# marqee_attiny85_new.net
KiCad netlist of a schematic drawn in EAGLE
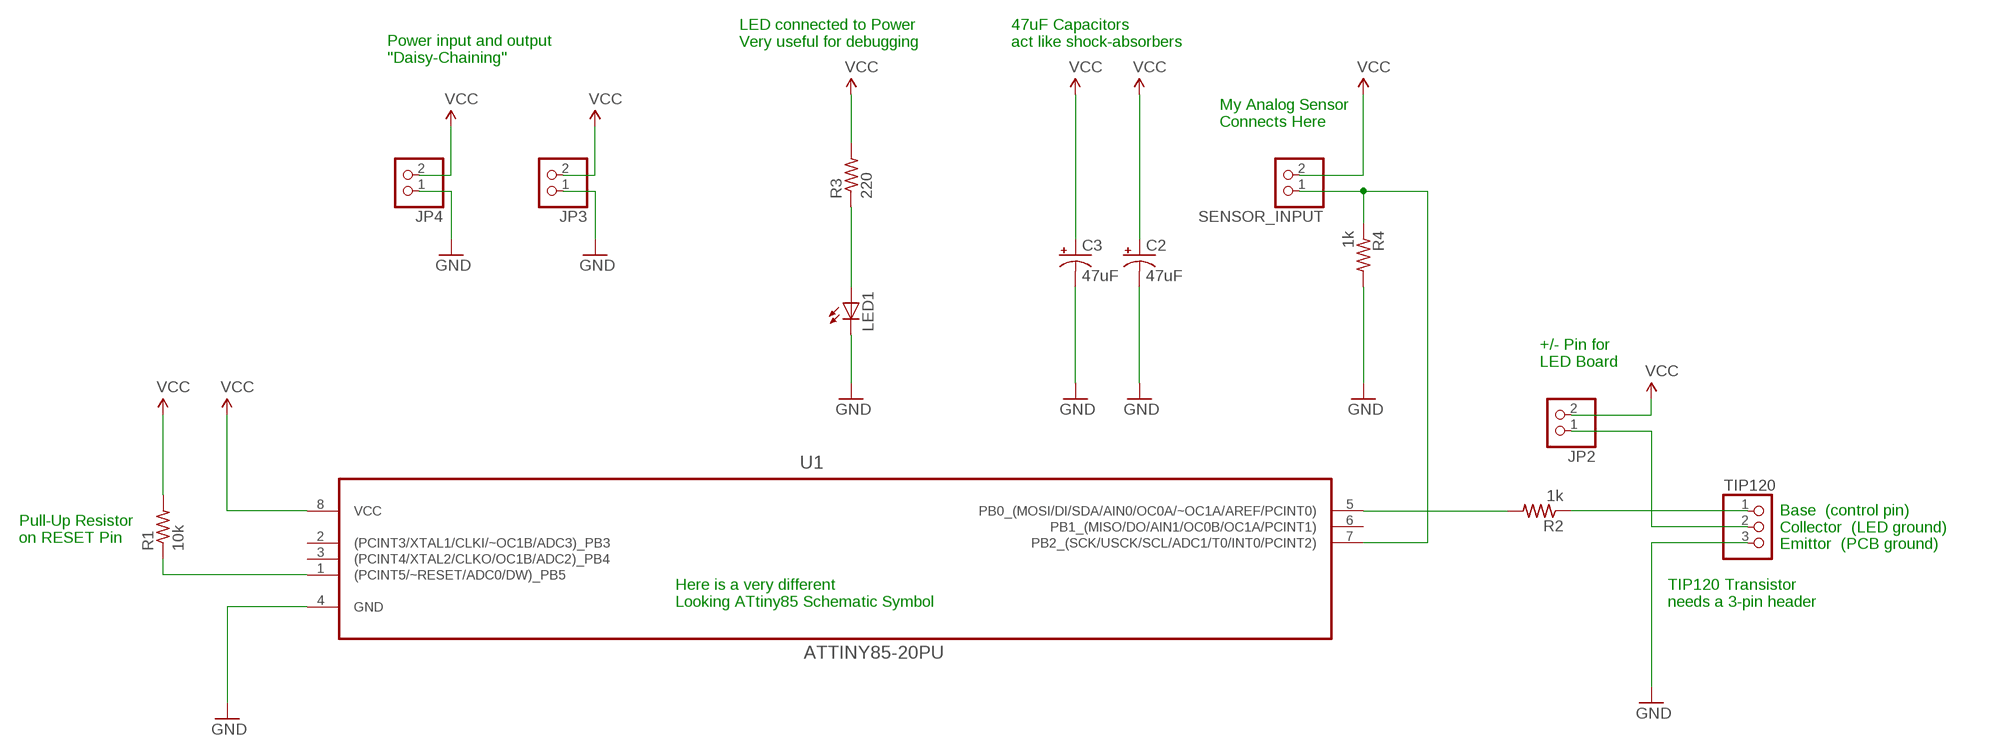
[diagram p0: schematic, sheet 1]

(export (version "E")
  (design (tool "Eeschema 10.0.6"))
  (components
    (comp (ref "C2")
      (value "47uF")
      (footprint "eagle-import:E5-8,5")
      (libsource (lib "eagle-import") (part "CPOL-USE5-8.5"))
    )
    (comp (ref "C3")
      (value "47uF")
      (footprint "eagle-import:E5-8,5")
      (libsource (lib "eagle-import") (part "CPOL-USE5-8.5"))
    )
    (comp (ref "JP2")
      (value "PINHD-1X2")
      (footprint "eagle-import:1X02")
      (libsource (lib "eagle-import") (part "PINHD-1X2"))
    )
    (comp (ref "JP3")
      (value "PINHD-1X2")
      (footprint "eagle-import:1X02")
      (libsource (lib "eagle-import") (part "PINHD-1X2"))
    )
    (comp (ref "JP4")
      (value "PINHD-1X2")
      (footprint "eagle-import:1X02")
      (libsource (lib "eagle-import") (part "PINHD-1X2"))
    )
    (comp (ref "LED1")
      (value "LED5MM")
      (footprint "eagle-import:LED5MM")
      (libsource (lib "eagle-import") (part "LED5MM"))
    )
    (comp (ref "R1")
      (value "10k")
      (footprint "eagle-import:0207_10")
      (libsource (lib "eagle-import") (part "R-US_0207/10"))
    )
    (comp (ref "R2")
      (value "1k")
      (footprint "eagle-import:0207_10")
      (libsource (lib "eagle-import") (part "R-US_0207/10"))
    )
    (comp (ref "R3")
      (value "220")
      (footprint "eagle-import:0207_10")
      (libsource (lib "eagle-import") (part "R-US_0207/10"))
    )
    (comp (ref "R4")
      (value "1k")
      (footprint "eagle-import:0207_10")
      (libsource (lib "eagle-import") (part "R-US_0207/10"))
    )
    (comp (ref "SENSOR_INPUT")
      (value "PINHD-1X2")
      (footprint "eagle-import:1X02")
      (libsource (lib "eagle-import") (part "PINHD-1X2"))
    )
    (comp (ref "TIP120")
      (value "PINHD-1X3")
      (footprint "eagle-import:1X03")
      (libsource (lib "eagle-import") (part "PINHD-1X3"))
    )
    (comp (ref "U1")
      (value "ATTINY85-20PU")
      (footprint "eagle-import:DIP254P762X533-8")
      (libsource (lib "eagle-import") (part "ATTINY85-20PU"))
    )
  )
  (nets
    (net (code "1") (name "GND") (class "Default")
      (node (ref "C2") (pin "-") (pinfunction "-_-") (pintype "passive"))
      (node (ref "C3") (pin "-") (pinfunction "-_-") (pintype "passive"))
      (node (ref "JP3") (pin "1") (pinfunction "1_1") (pintype "passive"))
      (node (ref "JP4") (pin "1") (pinfunction "1_1") (pintype "passive"))
      (node (ref "LED1") (pin "K") (pinfunction "C_K") (pintype "passive"))
      (node (ref "R4") (pin "2") (pinfunction "2_2") (pintype "passive"))
      (node (ref "TIP120") (pin "3") (pinfunction "3_3") (pintype "passive"))
      (node (ref "U1") (pin "4") (pinfunction "GND_4") (pintype "passive"))
    )
    (net (code "2") (name "Net-(JP2-Pad1)") (class "Default")
      (node (ref "JP2") (pin "1") (pinfunction "1_1") (pintype "passive"))
      (node (ref "TIP120") (pin "2") (pinfunction "2_2") (pintype "passive"))
    )
    (net (code "3") (name "Net-(LED1-PadA)") (class "Default")
      (node (ref "LED1") (pin "A") (pinfunction "A_A") (pintype "passive"))
      (node (ref "R3") (pin "1") (pinfunction "1_1") (pintype "passive"))
    )
    (net (code "4") (name "Net-(R2-Pad1)") (class "Default")
      (node (ref "R2") (pin "1") (pinfunction "1_1") (pintype "passive"))
      (node (ref "TIP120") (pin "1") (pinfunction "1_1") (pintype "passive"))
    )
    (net (code "5") (name "Net-(U1-(PCINT5{slash}~{RESET{slash}ADC0{slash}DW})_PB5)") (class "Default")
      (node (ref "R1") (pin "1") (pinfunction "1_1") (pintype "passive"))
      (node (ref "U1") (pin "1") (pinfunction "(PCINT5/~{RESET/ADC0/DW})_PB5_1") (pintype "bidirectional"))
    )
    (net (code "6") (name "Net-(U1-PB0_(MOSI{slash}DI{slash}SDA{slash}AIN0{slash}OC0A{slash}~{OC1A{slash}AREF{slash}PCINT0}))") (class "Default")
      (node (ref "R2") (pin "2") (pinfunction "2_2") (pintype "passive"))
      (node (ref "U1") (pin "5") (pinfunction "PB0_(MOSI/DI/SDA/AIN0/OC0A/~{OC1A/AREF/PCINT0})_5") (pintype "bidirectional"))
    )
    (net (code "7") (name "Net-(U1-PB2_(SCK{slash}USCK{slash}SCL{slash}ADC1{slash}T0{slash}INT0{slash}PCINT2))") (class "Default")
      (node (ref "R4") (pin "1") (pinfunction "1_1") (pintype "passive"))
      (node (ref "SENSOR_INPUT") (pin "1") (pinfunction "1_1") (pintype "passive"))
      (node (ref "U1") (pin "7") (pinfunction "PB2_(SCK/USCK/SCL/ADC1/T0/INT0/PCINT2)_7") (pintype "bidirectional"))
    )
    (net (code "8") (name "VCC") (class "Default")
      (node (ref "C2") (pin "+") (pinfunction "+_+") (pintype "passive"))
      (node (ref "C3") (pin "+") (pinfunction "+_+") (pintype "passive"))
      (node (ref "JP2") (pin "2") (pinfunction "2_2") (pintype "passive"))
      (node (ref "JP3") (pin "2") (pinfunction "2_2") (pintype "passive"))
      (node (ref "JP4") (pin "2") (pinfunction "2_2") (pintype "passive"))
      (node (ref "R1") (pin "2") (pinfunction "2_2") (pintype "passive"))
      (node (ref "R3") (pin "2") (pinfunction "2_2") (pintype "passive"))
      (node (ref "SENSOR_INPUT") (pin "2") (pinfunction "2_2") (pintype "passive"))
      (node (ref "U1") (pin "8") (pinfunction "VCC_8") (pintype "power_in"))
    )
    (net (code "9") (name "unconnected-(U1-(PCINT3{slash}XTAL1{slash}CLKI{slash}~{OC1B{slash}ADC3})_PB3-Pad2)") (class "Default")
      (node (ref "U1") (pin "2") (pinfunction "(PCINT3/XTAL1/CLKI/~{OC1B/ADC3})_PB3_2") (pintype "bidirectional"))
    )
    (net (code "10") (name "unconnected-(U1-(PCINT4{slash}XTAL2{slash}CLKO{slash}OC1B{slash}ADC2)_PB4-Pad3)") (class "Default")
      (node (ref "U1") (pin "3") (pinfunction "(PCINT4/XTAL2/CLKO/OC1B/ADC2)_PB4_3") (pintype "bidirectional"))
    )
    (net (code "11") (name "unconnected-(U1-PB1_(MISO{slash}DO{slash}AIN1{slash}OC0B{slash}OC1A{slash}PCINT1)-Pad6)") (class "Default")
      (node (ref "U1") (pin "6") (pinfunction "PB1_(MISO/DO/AIN1/OC0B/OC1A/PCINT1)_6") (pintype "bidirectional"))
    )
  )
)
